# Hall_effect_sensor.net
KiCad netlist of a schematic drawn in EAGLE
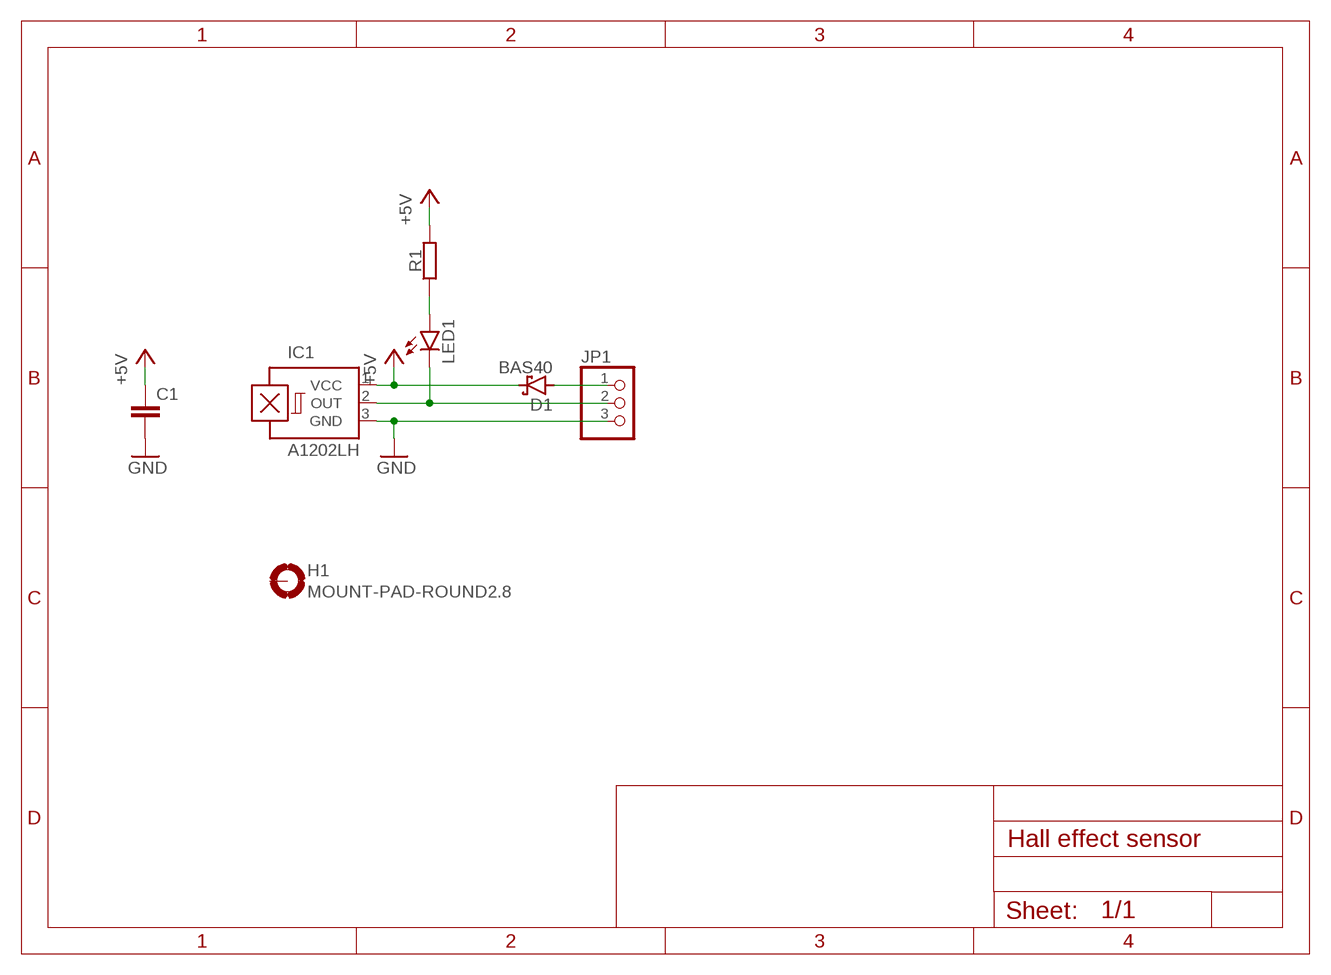
[diagram p0: schematic, sheet 1]

(export (version "E")
  (design (tool "Eeschema 10.0.6"))
  (components
    (comp (ref "C1")
      (value "C-EUC0805")
      (footprint "eagle-import:C0805")
      (libsource (lib "eagle-import") (part "C-EUC0805"))
    )
    (comp (ref "D1")
      (value "BAS40")
      (footprint "eagle-import:SOT23")
      (libsource (lib "eagle-import") (part "BAS40"))
    )
    (comp (ref "H1")
      (value "MOUNT-PAD-ROUND2.8")
      (footprint "eagle-import:2,8-PAD")
      (libsource (lib "eagle-import") (part "MOUNT-PAD-ROUND2.8"))
    )
    (comp (ref "IC1")
      (value "A1202LH")
      (footprint "eagle-import:SOT23-W")
      (libsource (lib "eagle-import") (part "A12?LH02"))
    )
    (comp (ref "JP1")
      (value "PINHD-1X3")
      (footprint "eagle-import:1X03")
      (libsource (lib "eagle-import") (part "PINHD-1X3"))
    )
    (comp (ref "LED1")
      (value "LEDCHIPLED_0603")
      (footprint "eagle-import:CHIPLED_0603")
      (libsource (lib "eagle-import") (part "LEDCHIPLED_0603"))
    )
    (comp (ref "R1")
      (value "RESISTORR0805-3D")
      (footprint "eagle-import:R0805")
      (libsource (lib "eagle-import") (part "RESISTORR0805-3D"))
    )
  )
  (nets
    (net (code "1") (name "+5V") (class "Default")
      (node (ref "C1") (pin "1") (pinfunction "1_1") (pintype "passive"))
      (node (ref "D1") (pin "3") (pinfunction "C_3") (pintype "passive"))
      (node (ref "IC1") (pin "1") (pinfunction "VCC_1") (pintype "power_in"))
      (node (ref "R1") (pin "2") (pinfunction "2_2") (pintype "passive"))
    )
    (net (code "2") (name "GND") (class "Default")
      (node (ref "C1") (pin "2") (pinfunction "2_2") (pintype "passive"))
      (node (ref "IC1") (pin "3") (pinfunction "GND_3") (pintype "power_in"))
      (node (ref "JP1") (pin "3") (pinfunction "3_3") (pintype "passive"))
    )
    (net (code "3") (name "Net-(D1-A)") (class "Default")
      (node (ref "D1") (pin "1") (pinfunction "A_1") (pintype "passive"))
      (node (ref "JP1") (pin "1") (pinfunction "1_1") (pintype "passive"))
    )
    (net (code "4") (name "Net-(IC1-OUT)") (class "Default")
      (node (ref "IC1") (pin "2") (pinfunction "OUT_2") (pintype "output"))
      (node (ref "JP1") (pin "2") (pinfunction "2_2") (pintype "passive"))
      (node (ref "LED1") (pin "C") (pinfunction "C_C") (pintype "passive"))
    )
    (net (code "5") (name "Net-(LED1-PadA)") (class "Default")
      (node (ref "LED1") (pin "A") (pinfunction "A_A") (pintype "passive"))
      (node (ref "R1") (pin "1") (pinfunction "1_1") (pintype "passive"))
    )
    (net (code "6") (name "unconnected-(H1-MOUNT-PadB2,8)") (class "Default")
      (node (ref "H1") (pin "B2,8") (pinfunction "MOUNT_B2,8") (pintype "passive"))
    )
  )
)
